# f1c200s_V1_1.net
KiCad netlist of a schematic drawn in EasyEDA Pro
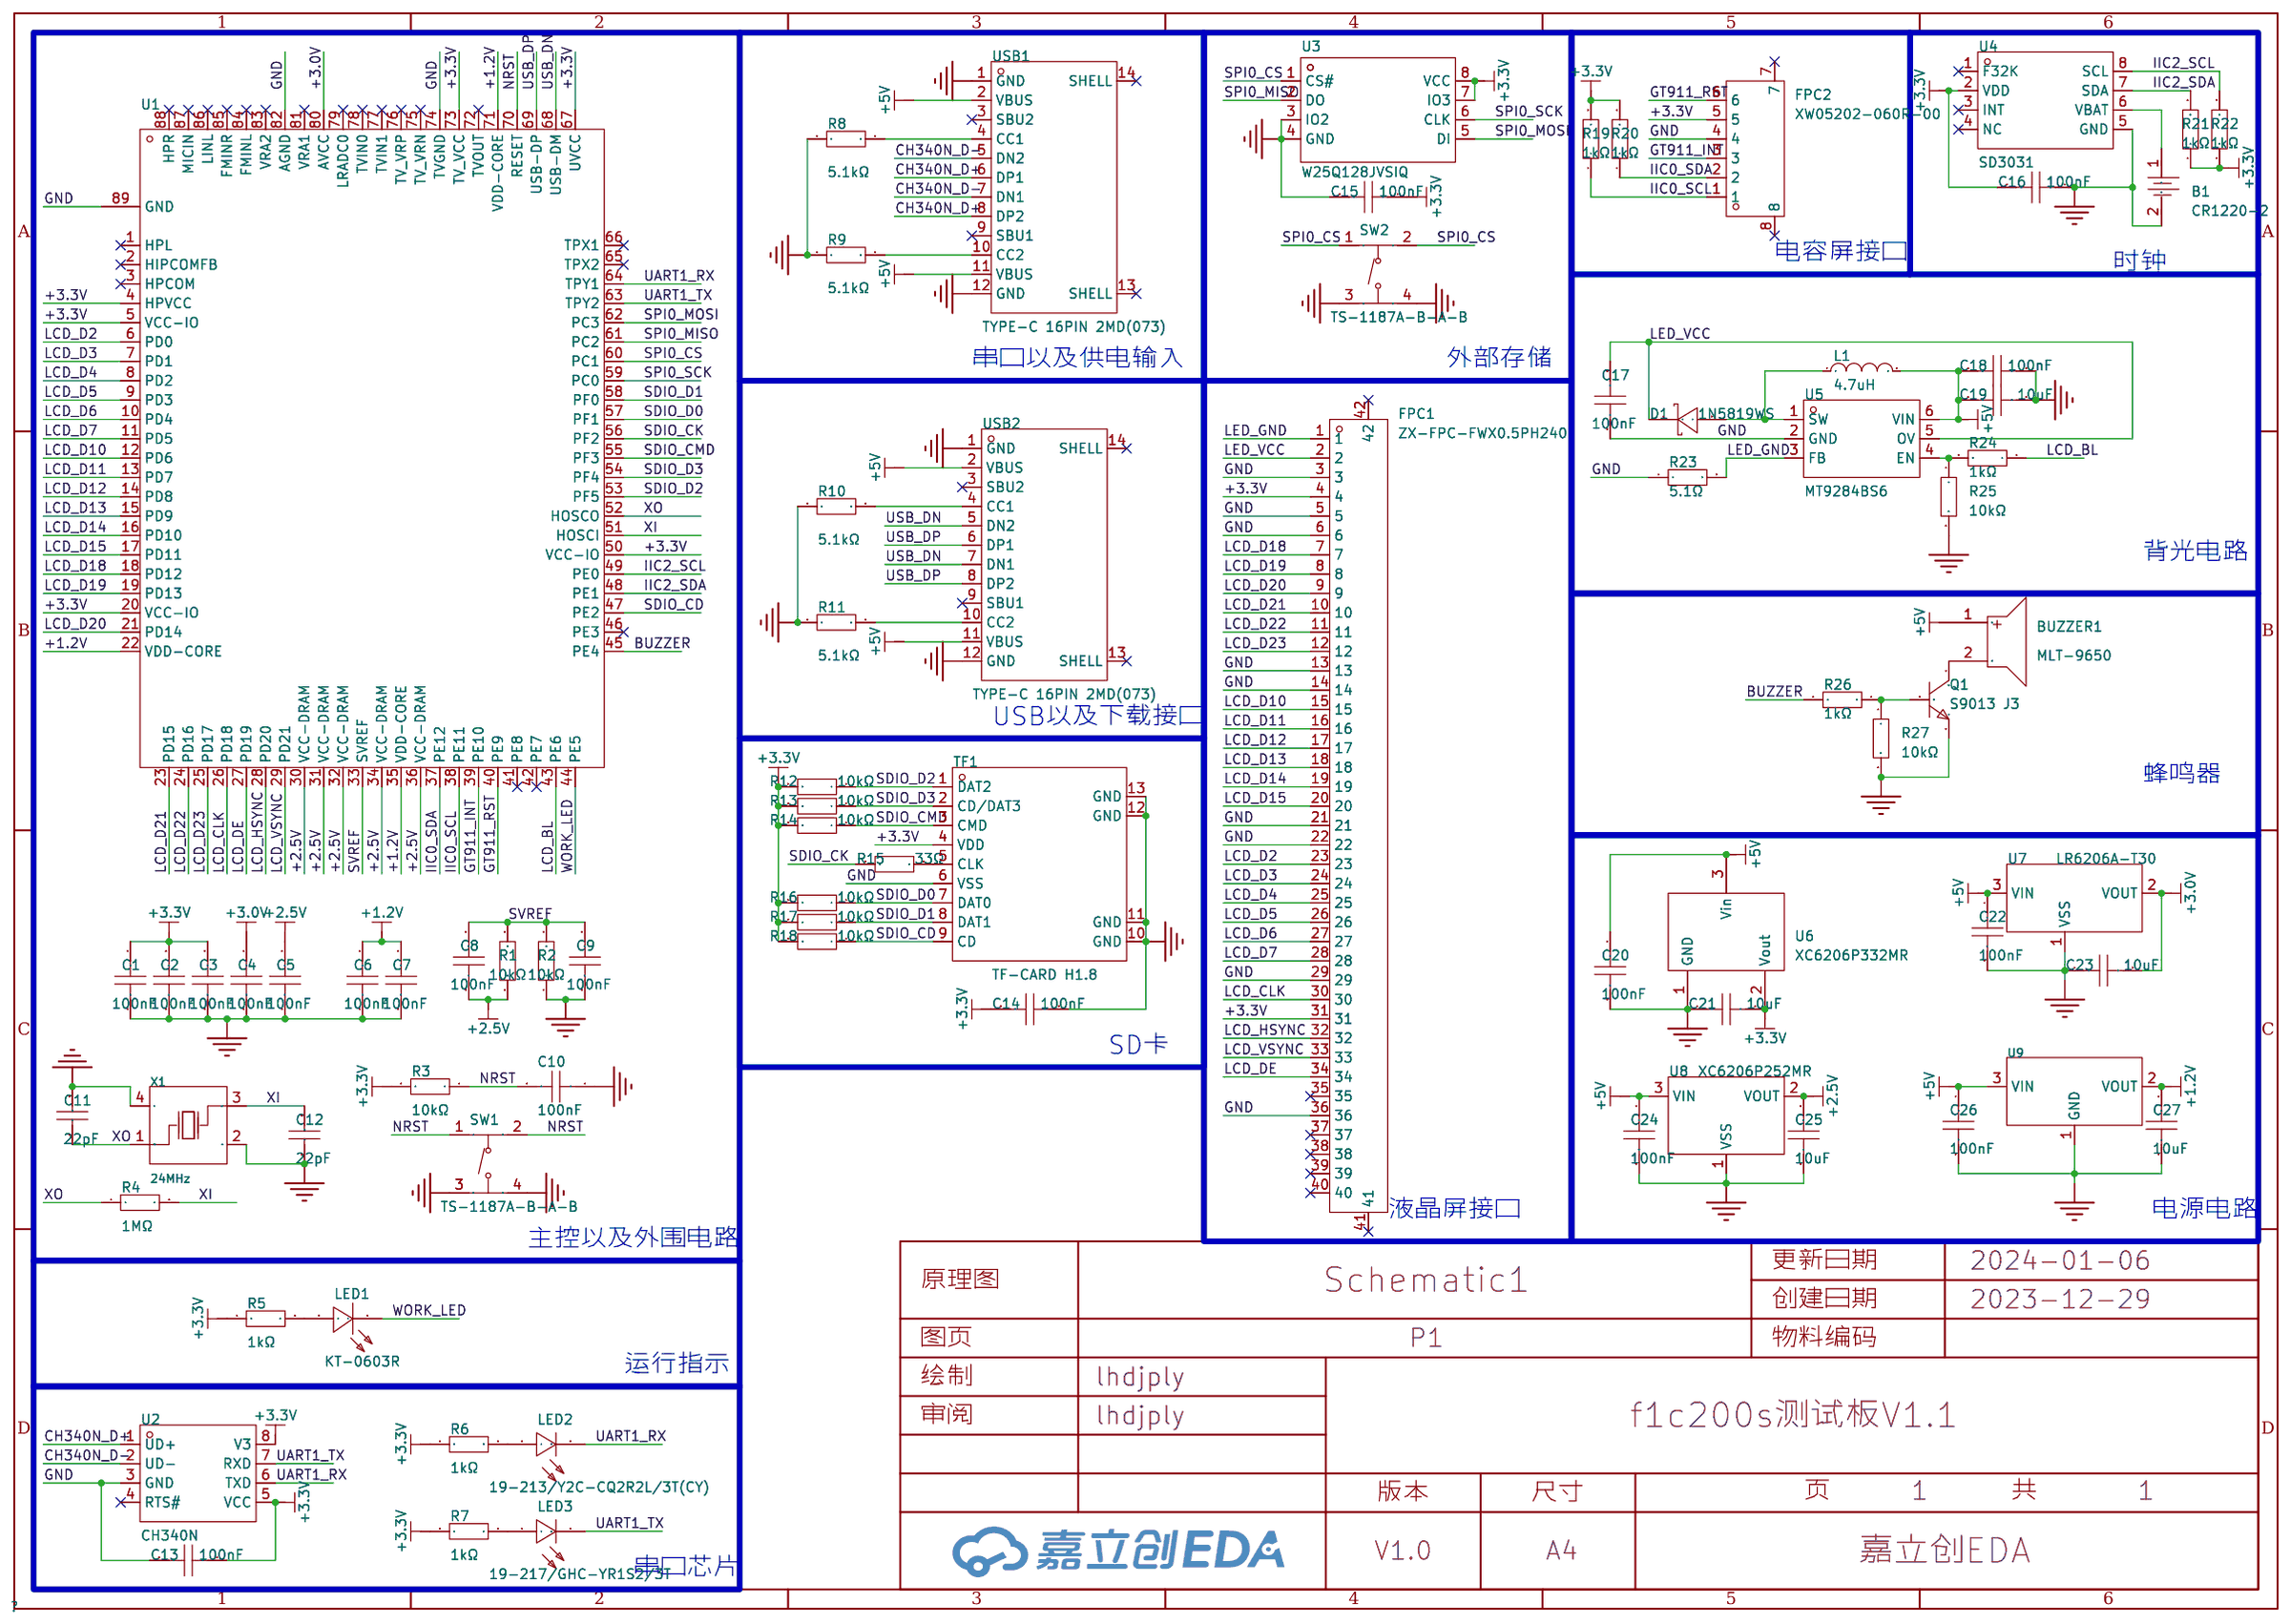
[diagram p0: schematic sheet]

(export (version "E")
  (design (tool "Eeschema 10.0.6"))
  (components
    (comp (ref "B1")
      (value "CR1220-2")
      (footprint "easyedapro:BAT-SMD_CR1220-2")
      (description "连接器类型:电池底座;适用电池规格:CR1220;工作温度范围:-;")
      (fields (field (name "Manufacturer") "Q&amp;J"))
      (libsource (lib "easyedapro") (part "CR1220-2"))
    )
    (comp (ref "BUZZER1")
      (value "2700Hz")
      (footprint "easyedapro:BUZ-SMD_L9.6-W9.6-LS10.0-R")
      (fields (field (name "Manufacturer Part") "MLT-9650") (field (name "Manufacturer") "华能"))
      (libsource (lib "easyedapro") (part "HND-9650B"))
    )
    (comp (ref "C1")
      (value "100nF")
      (footprint "easyedapro:C0603")
      (description "容值:100nF;精度:±10%;额定电压:50V;材质(温度系数):X7R;")
      (fields
        (field (name "Manufacturer Part") "CC0603KRX7R9BB104")
        (field (name "Manufacturer") "YAGEO(国巨)")
      )
      (libsource (lib "easyedapro") (part "CC0603KRX7R9BB104"))
    )
    (comp (ref "C2")
      (value "100nF")
      (footprint "easyedapro:C0603")
      (description "容值:100nF;精度:±10%;额定电压:50V;材质(温度系数):X7R;")
      (fields
        (field (name "Manufacturer Part") "CC0603KRX7R9BB104")
        (field (name "Manufacturer") "YAGEO(国巨)")
      )
      (libsource (lib "easyedapro") (part "CC0603KRX7R9BB104"))
    )
    (comp (ref "C3")
      (value "100nF")
      (footprint "easyedapro:C0603")
      (description "容值:100nF;精度:±10%;额定电压:50V;材质(温度系数):X7R;")
      (fields
        (field (name "Manufacturer Part") "CC0603KRX7R9BB104")
        (field (name "Manufacturer") "YAGEO(国巨)")
      )
      (libsource (lib "easyedapro") (part "CC0603KRX7R9BB104"))
    )
    (comp (ref "C4")
      (value "100nF")
      (footprint "easyedapro:C0603")
      (description "容值:100nF;精度:±10%;额定电压:50V;材质(温度系数):X7R;")
      (fields
        (field (name "Manufacturer Part") "CC0603KRX7R9BB104")
        (field (name "Manufacturer") "YAGEO(国巨)")
      )
      (libsource (lib "easyedapro") (part "CC0603KRX7R9BB104"))
    )
    (comp (ref "C5")
      (value "100nF")
      (footprint "easyedapro:C0603")
      (description "容值:100nF;精度:±10%;额定电压:50V;材质(温度系数):X7R;")
      (fields
        (field (name "Manufacturer Part") "CC0603KRX7R9BB104")
        (field (name "Manufacturer") "YAGEO(国巨)")
      )
      (libsource (lib "easyedapro") (part "CC0603KRX7R9BB104"))
    )
    (comp (ref "C6")
      (value "100nF")
      (footprint "easyedapro:C0603")
      (description "容值:100nF;精度:±10%;额定电压:50V;材质(温度系数):X7R;")
      (fields
        (field (name "Manufacturer Part") "CC0603KRX7R9BB104")
        (field (name "Manufacturer") "YAGEO(国巨)")
      )
      (libsource (lib "easyedapro") (part "CC0603KRX7R9BB104"))
    )
    (comp (ref "C7")
      (value "100nF")
      (footprint "easyedapro:C0603")
      (description "容值:100nF;精度:±10%;额定电压:50V;材质(温度系数):X7R;")
      (fields
        (field (name "Manufacturer Part") "CC0603KRX7R9BB104")
        (field (name "Manufacturer") "YAGEO(国巨)")
      )
      (libsource (lib "easyedapro") (part "CC0603KRX7R9BB104"))
    )
    (comp (ref "C8")
      (value "100nF")
      (footprint "easyedapro:C0603")
      (description "容值:100nF;精度:±10%;额定电压:50V;材质(温度系数):X7R;")
      (fields
        (field (name "Manufacturer Part") "CC0603KRX7R9BB104")
        (field (name "Manufacturer") "YAGEO(国巨)")
      )
      (libsource (lib "easyedapro") (part "CC0603KRX7R9BB104"))
    )
    (comp (ref "C9")
      (value "100nF")
      (footprint "easyedapro:C0603")
      (description "容值:100nF;精度:±10%;额定电压:50V;材质(温度系数):X7R;")
      (fields
        (field (name "Manufacturer Part") "CC0603KRX7R9BB104")
        (field (name "Manufacturer") "YAGEO(国巨)")
      )
      (libsource (lib "easyedapro") (part "CC0603KRX7R9BB104"))
    )
    (comp (ref "C10")
      (value "100nF")
      (footprint "easyedapro:C0603")
      (description "容值:100nF;精度:±10%;额定电压:50V;材质(温度系数):X7R;")
      (fields
        (field (name "Manufacturer Part") "CC0603KRX7R9BB104")
        (field (name "Manufacturer") "YAGEO(国巨)")
      )
      (libsource (lib "easyedapro") (part "CC0603KRX7R9BB104"))
    )
    (comp (ref "C11")
      (value "22pF")
      (footprint "easyedapro:C0603")
      (description "容值:22pF;精度:±5%;额定电压:50V;材质(温度系数):C0G;")
      (fields
        (field (name "Manufacturer Part") "CL10C220JB8NNNC")
        (field (name "Manufacturer") "SAMSUNG(三星)")
      )
      (libsource (lib "easyedapro") (part "CL10C220JB8NNNC"))
    )
    (comp (ref "C12")
      (value "22pF")
      (footprint "easyedapro:C0603")
      (description "容值:22pF;精度:±5%;额定电压:50V;材质(温度系数):C0G;")
      (fields
        (field (name "Manufacturer Part") "CL10C220JB8NNNC")
        (field (name "Manufacturer") "SAMSUNG(三星)")
      )
      (libsource (lib "easyedapro") (part "CL10C220JB8NNNC"))
    )
    (comp (ref "C13")
      (value "100nF")
      (footprint "easyedapro:C0603")
      (description "容值:100nF;精度:±10%;额定电压:50V;材质(温度系数):X7R;")
      (fields
        (field (name "Manufacturer Part") "CC0603KRX7R9BB104")
        (field (name "Manufacturer") "YAGEO(国巨)")
      )
      (libsource (lib "easyedapro") (part "CC0603KRX7R9BB104"))
    )
    (comp (ref "C14")
      (value "100nF")
      (footprint "easyedapro:C0603")
      (description "容值:100nF;精度:±10%;额定电压:50V;材质(温度系数):X7R;")
      (fields
        (field (name "Manufacturer Part") "CC0603KRX7R9BB104")
        (field (name "Manufacturer") "YAGEO(国巨)")
      )
      (libsource (lib "easyedapro") (part "CC0603KRX7R9BB104"))
    )
    (comp (ref "C15")
      (value "100nF")
      (footprint "easyedapro:C0603")
      (description "容值:100nF;精度:±10%;额定电压:50V;材质(温度系数):X7R;")
      (fields
        (field (name "Manufacturer Part") "CC0603KRX7R9BB104")
        (field (name "Manufacturer") "YAGEO(国巨)")
      )
      (libsource (lib "easyedapro") (part "CC0603KRX7R9BB104"))
    )
    (comp (ref "C16")
      (value "100nF")
      (footprint "easyedapro:C0603")
      (description "容值:100nF;精度:±10%;额定电压:50V;材质(温度系数):X7R;")
      (fields
        (field (name "Manufacturer Part") "CC0603KRX7R9BB104")
        (field (name "Manufacturer") "YAGEO(国巨)")
      )
      (libsource (lib "easyedapro") (part "CC0603KRX7R9BB104"))
    )
    (comp (ref "C17")
      (value "100nF")
      (footprint "easyedapro:C0603")
      (description "容值:100nF;精度:±10%;额定电压:50V;材质(温度系数):X7R;")
      (fields
        (field (name "Manufacturer Part") "CC0603KRX7R9BB104")
        (field (name "Manufacturer") "YAGEO(国巨)")
      )
      (libsource (lib "easyedapro") (part "CC0603KRX7R9BB104"))
    )
    (comp (ref "C18")
      (value "100nF")
      (footprint "easyedapro:C0603")
      (description "容值:100nF;精度:±10%;额定电压:50V;材质(温度系数):X7R;")
      (fields
        (field (name "Manufacturer Part") "CC0603KRX7R9BB104")
        (field (name "Manufacturer") "YAGEO(国巨)")
      )
      (libsource (lib "easyedapro") (part "CC0603KRX7R9BB104"))
    )
    (comp (ref "C19")
      (value "10uF")
      (footprint "easyedapro:C0603")
      (description "容值:10uF;精度:±10%;额定电压:10V;材质(温度系数):X5R;")
      (fields
        (field (name "Manufacturer Part") "CL10A106KP8NNNC")
        (field (name "Manufacturer") "SAMSUNG(三星)")
      )
      (libsource (lib "easyedapro") (part "CL10A106KP8NNNC"))
    )
    (comp (ref "C20")
      (value "100nF")
      (footprint "easyedapro:C0603")
      (description "容值:100nF;精度:±10%;额定电压:50V;材质(温度系数):X7R;")
      (fields
        (field (name "Manufacturer Part") "CC0603KRX7R9BB104")
        (field (name "Manufacturer") "YAGEO(国巨)")
      )
      (libsource (lib "easyedapro") (part "CC0603KRX7R9BB104"))
    )
    (comp (ref "C21")
      (value "10uF")
      (footprint "easyedapro:C0603")
      (description "容值:10uF;精度:±10%;额定电压:10V;材质(温度系数):X5R;")
      (fields
        (field (name "Manufacturer Part") "CL10A106KP8NNNC")
        (field (name "Manufacturer") "SAMSUNG(三星)")
      )
      (libsource (lib "easyedapro") (part "CL10A106KP8NNNC"))
    )
    (comp (ref "C22")
      (value "100nF")
      (footprint "easyedapro:C0603")
      (description "容值:100nF;精度:±10%;额定电压:50V;材质(温度系数):X7R;")
      (fields
        (field (name "Manufacturer Part") "CC0603KRX7R9BB104")
        (field (name "Manufacturer") "YAGEO(国巨)")
      )
      (libsource (lib "easyedapro") (part "CC0603KRX7R9BB104"))
    )
    (comp (ref "C23")
      (value "10uF")
      (footprint "easyedapro:C0603")
      (description "容值:10uF;精度:±10%;额定电压:10V;材质(温度系数):X5R;")
      (fields
        (field (name "Manufacturer Part") "CL10A106KP8NNNC")
        (field (name "Manufacturer") "SAMSUNG(三星)")
      )
      (libsource (lib "easyedapro") (part "CL10A106KP8NNNC"))
    )
    (comp (ref "C24")
      (value "100nF")
      (footprint "easyedapro:C0603")
      (description "容值:100nF;精度:±10%;额定电压:50V;材质(温度系数):X7R;")
      (fields
        (field (name "Manufacturer Part") "CC0603KRX7R9BB104")
        (field (name "Manufacturer") "YAGEO(国巨)")
      )
      (libsource (lib "easyedapro") (part "CC0603KRX7R9BB104"))
    )
    (comp (ref "C25")
      (value "10uF")
      (footprint "easyedapro:C0603")
      (description "容值:10uF;精度:±10%;额定电压:10V;材质(温度系数):X5R;")
      (fields
        (field (name "Manufacturer Part") "CL10A106KP8NNNC")
        (field (name "Manufacturer") "SAMSUNG(三星)")
      )
      (libsource (lib "easyedapro") (part "CL10A106KP8NNNC"))
    )
    (comp (ref "C26")
      (value "100nF")
      (footprint "easyedapro:C0603")
      (description "容值:100nF;精度:±10%;额定电压:50V;材质(温度系数):X7R;")
      (fields
        (field (name "Manufacturer Part") "CC0603KRX7R9BB104")
        (field (name "Manufacturer") "YAGEO(国巨)")
      )
      (libsource (lib "easyedapro") (part "CC0603KRX7R9BB104"))
    )
    (comp (ref "C27")
      (value "10uF")
      (footprint "easyedapro:C0603")
      (description "容值:10uF;精度:±10%;额定电压:10V;材质(温度系数):X5R;")
      (fields
        (field (name "Manufacturer Part") "CL10A106KP8NNNC")
        (field (name "Manufacturer") "SAMSUNG(三星)")
      )
      (libsource (lib "easyedapro") (part "CL10A106KP8NNNC"))
    )
    (comp (ref "D1")
      (value "1N5819WS")
      (footprint "easyedapro:SOD-323_L1.8-W1.3-LS2.5-RD")
      (description "正向压降(Vf):600mV@1A;直流反向耐压(Vr):40V;平均整流电流(Io):1A;")
      (fields (field (name "Manufacturer") "Hottech(合科泰)"))
      (libsource (lib "easyedapro") (part "1N5819WS"))
    )
    (comp (ref "FPC1")
      (value "ZX-FPC-FWX0.5PH240")
      (footprint "easyedapro:FPC-SMD_40P-P0.50_MEGASTAR_ZX-FPC-FWX0.5PH240")
      (description "间距:0.5mm;触点数量:40P;锁定特性:翻盖式;触点类型:下接;安装类型:卧贴;工作温度范围:-25°C~+85°C;焊接温度(最大值):260°C;")
      (fields (field (name "Manufacturer") "Megastar(兆星)"))
      (libsource (lib "easyedapro") (part "ZX-FPC-FWX0.5PH240"))
    )
    (comp (ref "FPC2")
      (value "XW05202-060R-00")
      (footprint "easyedapro:FPC-SMD_XW05202-060R-00")
      (description "间距:0.5mm;触点数量:6P;锁定特性:翻盖式;触点类型:下接;安装类型:卧贴;工作温度范围:-25°C~+85°C;")
      (fields (field (name "Manufacturer") "HCTL(华灿天禄)"))
      (libsource (lib "easyedapro") (part "XW05202-060R-00"))
    )
    (comp (ref "L1")
      (value "4.7uH")
      (footprint "easyedapro:IND-SMD_L5.8-W5.2_SLF05XX")
      (description "电感值:4.7uH;精度:±20%;额定电流:3A;饱和电流(Isat):3A;")
      (fields (field (name "Manufacturer Part") "CD54N-4R7M") (field (name "Manufacturer") "MINGSTAR(登壹)"))
      (libsource (lib "easyedapro") (part "CD54N-4R7M"))
    )
    (comp (ref "LED1")
      (value "KT-0603R")
      (footprint "easyedapro:LED0603-RD")
      (description "发光颜色:红灯;二极管配置:-;透镜颜色:-;主波长:-;色温:-;功率:-;发光角度:-;安装方式:-;工作温度:-40°C~+85°C;")
      (fields (field (name "Manufacturer") "KENTO"))
      (libsource (lib "easyedapro") (part "KT-0603R"))
    )
    (comp (ref "LED2")
      (value "19-213/Y2C-CQ2R2L/3T(CY)")
      (footprint "easyedapro:LED0603-RD-YELLOW")
      (description "发光颜色:黄灯;二极管配置:-;主波长:585.5nm~591.5nm;色温:-;功率:60mW;安装方式:-;")
      (fields (field (name "Manufacturer") "EVERLIGHT(亿光)"))
      (libsource (lib "easyedapro") (part "19-213/Y2C-CQ2R2L/3T(CY)"))
    )
    (comp (ref "LED3")
      (value "19-217/GHC-YR1S2/3T")
      (footprint "easyedapro:LED0603-RD")
      (fields (field (name "Manufacturer") "EVERLIGHT(亿光)"))
      (libsource (lib "easyedapro") (part "19-217/GHC-YR1S2/3T"))
    )
    (comp (ref "Q1")
      (value "S9013 J3")
      (footprint "easyedapro:SOT-23-3_L2.9-W1.3-P1.90-LS2.4-BR")
      (description "晶体管类型:NPN;集电极电流(Ic):500mA;集射极击穿电压(Vceo):25V;功率(Pd):300mW;直流电流增益(hFE@Ic,Vce):200@50mA,1V;")
      (fields (field (name "Manufacturer") "CJ(江苏长电/长晶)"))
      (libsource (lib "easyedapro") (part "S9013 J3"))
    )
    (comp (ref "R1")
      (value "10kΩ")
      (footprint "easyedapro:R0603")
      (description "阻值:10kΩ;精度:±1%;功率:100mW;温度系数:±100ppm/°C;电阻类型:厚膜电阻;")
      (fields
        (field (name "Manufacturer Part") "0603WAF1002T5E")
        (field (name "Manufacturer") "UNI-ROYAL(厚声)")
      )
      (libsource (lib "easyedapro") (part "0603WAF1002T5E"))
    )
    (comp (ref "R2")
      (value "10kΩ")
      (footprint "easyedapro:R0603")
      (description "阻值:10kΩ;精度:±1%;功率:100mW;温度系数:±100ppm/°C;电阻类型:厚膜电阻;")
      (fields
        (field (name "Manufacturer Part") "0603WAF1002T5E")
        (field (name "Manufacturer") "UNI-ROYAL(厚声)")
      )
      (libsource (lib "easyedapro") (part "0603WAF1002T5E"))
    )
    (comp (ref "R3")
      (value "10kΩ")
      (footprint "easyedapro:R0603")
      (description "阻值:10kΩ;精度:±1%;功率:100mW;温度系数:±100ppm/°C;电阻类型:厚膜电阻;")
      (fields
        (field (name "Manufacturer Part") "0603WAF1002T5E")
        (field (name "Manufacturer") "UNI-ROYAL(厚声)")
      )
      (libsource (lib "easyedapro") (part "0603WAF1002T5E"))
    )
    (comp (ref "R4")
      (value "1MΩ")
      (footprint "easyedapro:R0603")
      (description "阻值:1MΩ;精度:±1%;功率:100mW;温度系数:±100ppm/°C;电阻类型:厚膜电阻;")
      (fields
        (field (name "Manufacturer Part") "0603WAF1004T5E")
        (field (name "Manufacturer") "UNI-ROYAL(厚声)")
      )
      (libsource (lib "easyedapro") (part "0603WAF1004T5E"))
    )
    (comp (ref "R5")
      (value "1kΩ")
      (footprint "easyedapro:R0603")
      (description "阻值:1kΩ;精度:±1%;功率:100mW;温度系数:±100ppm/°C;电阻类型:厚膜电阻;")
      (fields
        (field (name "Manufacturer Part") "0603WAF1001T5E")
        (field (name "Manufacturer") "UNI-ROYAL(厚声)")
      )
      (libsource (lib "easyedapro") (part "0603WAF1001T5E"))
    )
    (comp (ref "R6")
      (value "1kΩ")
      (footprint "easyedapro:R0603")
      (description "阻值:1kΩ;精度:±1%;功率:100mW;温度系数:±100ppm/°C;电阻类型:厚膜电阻;")
      (fields
        (field (name "Manufacturer Part") "0603WAF1001T5E")
        (field (name "Manufacturer") "UNI-ROYAL(厚声)")
      )
      (libsource (lib "easyedapro") (part "0603WAF1001T5E"))
    )
    (comp (ref "R7")
      (value "1kΩ")
      (footprint "easyedapro:R0603")
      (description "阻值:1kΩ;精度:±1%;功率:100mW;温度系数:±100ppm/°C;电阻类型:厚膜电阻;")
      (fields
        (field (name "Manufacturer Part") "0603WAF1001T5E")
        (field (name "Manufacturer") "UNI-ROYAL(厚声)")
      )
      (libsource (lib "easyedapro") (part "0603WAF1001T5E"))
    )
    (comp (ref "R8")
      (value "5.1kΩ")
      (footprint "easyedapro:R0603")
      (description "阻值:5.1kΩ;精度:±1%;功率:100mW;温度系数:±100ppm/°C;电阻类型:厚膜电阻;")
      (fields
        (field (name "Manufacturer Part") "0603WAF5101T5E")
        (field (name "Manufacturer") "UNI-ROYAL(厚声)")
      )
      (libsource (lib "easyedapro") (part "0603WAF5101T5E"))
    )
    (comp (ref "R9")
      (value "5.1kΩ")
      (footprint "easyedapro:R0603")
      (description "阻值:5.1kΩ;精度:±1%;功率:100mW;温度系数:±100ppm/°C;电阻类型:厚膜电阻;")
      (fields
        (field (name "Manufacturer Part") "0603WAF5101T5E")
        (field (name "Manufacturer") "UNI-ROYAL(厚声)")
      )
      (libsource (lib "easyedapro") (part "0603WAF5101T5E"))
    )
    (comp (ref "R10")
      (value "5.1kΩ")
      (footprint "easyedapro:R0603")
      (description "阻值:5.1kΩ;精度:±1%;功率:100mW;温度系数:±100ppm/°C;电阻类型:厚膜电阻;")
      (fields
        (field (name "Manufacturer Part") "0603WAF5101T5E")
        (field (name "Manufacturer") "UNI-ROYAL(厚声)")
      )
      (libsource (lib "easyedapro") (part "0603WAF5101T5E"))
    )
    (comp (ref "R11")
      (value "5.1kΩ")
      (footprint "easyedapro:R0603")
      (description "阻值:5.1kΩ;精度:±1%;功率:100mW;温度系数:±100ppm/°C;电阻类型:厚膜电阻;")
      (fields
        (field (name "Manufacturer Part") "0603WAF5101T5E")
        (field (name "Manufacturer") "UNI-ROYAL(厚声)")
      )
      (libsource (lib "easyedapro") (part "0603WAF5101T5E"))
    )
    (comp (ref "R12")
      (value "10kΩ")
      (footprint "easyedapro:R0603")
      (description "阻值:10kΩ;精度:±1%;功率:100mW;温度系数:±100ppm/°C;电阻类型:厚膜电阻;")
      (fields
        (field (name "Manufacturer Part") "0603WAF1002T5E")
        (field (name "Manufacturer") "UNI-ROYAL(厚声)")
      )
      (libsource (lib "easyedapro") (part "0603WAF1002T5E"))
    )
    (comp (ref "R13")
      (value "10kΩ")
      (footprint "easyedapro:R0603")
      (description "阻值:10kΩ;精度:±1%;功率:100mW;温度系数:±100ppm/°C;电阻类型:厚膜电阻;")
      (fields
        (field (name "Manufacturer Part") "0603WAF1002T5E")
        (field (name "Manufacturer") "UNI-ROYAL(厚声)")
      )
      (libsource (lib "easyedapro") (part "0603WAF1002T5E"))
    )
    (comp (ref "R14")
      (value "10kΩ")
      (footprint "easyedapro:R0603")
      (description "阻值:10kΩ;精度:±1%;功率:100mW;温度系数:±100ppm/°C;电阻类型:厚膜电阻;")
      (fields
        (field (name "Manufacturer Part") "0603WAF1002T5E")
        (field (name "Manufacturer") "UNI-ROYAL(厚声)")
      )
      (libsource (lib "easyedapro") (part "0603WAF1002T5E"))
    )
    (comp (ref "R15")
      (value "33Ω")
      (footprint "easyedapro:R0603")
      (description "阻值:33Ω;精度:±1%;功率:100mW;温度系数:±100ppm/°C;电阻类型:厚膜电阻;")
      (fields
        (field (name "Manufacturer Part") "0603WAF330JT5E")
        (field (name "Manufacturer") "UNI-ROYAL(厚声)")
      )
      (libsource (lib "easyedapro") (part "0603WAF330JT5E"))
    )
    (comp (ref "R16")
      (value "10kΩ")
      (footprint "easyedapro:R0603")
      (description "阻值:10kΩ;精度:±1%;功率:100mW;温度系数:±100ppm/°C;电阻类型:厚膜电阻;")
      (fields
        (field (name "Manufacturer Part") "0603WAF1002T5E")
        (field (name "Manufacturer") "UNI-ROYAL(厚声)")
      )
      (libsource (lib "easyedapro") (part "0603WAF1002T5E"))
    )
    (comp (ref "R17")
      (value "10kΩ")
      (footprint "easyedapro:R0603")
      (description "阻值:10kΩ;精度:±1%;功率:100mW;温度系数:±100ppm/°C;电阻类型:厚膜电阻;")
      (fields
        (field (name "Manufacturer Part") "0603WAF1002T5E")
        (field (name "Manufacturer") "UNI-ROYAL(厚声)")
      )
      (libsource (lib "easyedapro") (part "0603WAF1002T5E"))
    )
    (comp (ref "R18")
      (value "10kΩ")
      (footprint "easyedapro:R0603")
      (description "阻值:10kΩ;精度:±1%;功率:100mW;温度系数:±100ppm/°C;电阻类型:厚膜电阻;")
      (fields
        (field (name "Manufacturer Part") "0603WAF1002T5E")
        (field (name "Manufacturer") "UNI-ROYAL(厚声)")
      )
      (libsource (lib "easyedapro") (part "0603WAF1002T5E"))
    )
    (comp (ref "R19")
      (value "1kΩ")
      (footprint "easyedapro:R0603")
      (description "阻值:1kΩ;精度:±1%;功率:100mW;温度系数:±100ppm/°C;电阻类型:厚膜电阻;")
      (fields
        (field (name "Manufacturer Part") "0603WAF1001T5E")
        (field (name "Manufacturer") "UNI-ROYAL(厚声)")
      )
      (libsource (lib "easyedapro") (part "0603WAF1001T5E"))
    )
    (comp (ref "R20")
      (value "1kΩ")
      (footprint "easyedapro:R0603")
      (description "阻值:1kΩ;精度:±1%;功率:100mW;温度系数:±100ppm/°C;电阻类型:厚膜电阻;")
      (fields
        (field (name "Manufacturer Part") "0603WAF1001T5E")
        (field (name "Manufacturer") "UNI-ROYAL(厚声)")
      )
      (libsource (lib "easyedapro") (part "0603WAF1001T5E"))
    )
    (comp (ref "R21")
      (value "1kΩ")
      (footprint "easyedapro:R0603")
      (description "阻值:1kΩ;精度:±1%;功率:100mW;温度系数:±100ppm/°C;电阻类型:厚膜电阻;")
      (fields
        (field (name "Manufacturer Part") "0603WAF1001T5E")
        (field (name "Manufacturer") "UNI-ROYAL(厚声)")
      )
      (libsource (lib "easyedapro") (part "0603WAF1001T5E"))
    )
    (comp (ref "R22")
      (value "1kΩ")
      (footprint "easyedapro:R0603")
      (description "阻值:1kΩ;精度:±1%;功率:100mW;温度系数:±100ppm/°C;电阻类型:厚膜电阻;")
      (fields
        (field (name "Manufacturer Part") "0603WAF1001T5E")
        (field (name "Manufacturer") "UNI-ROYAL(厚声)")
      )
      (libsource (lib "easyedapro") (part "0603WAF1001T5E"))
    )
    (comp (ref "R23")
      (value "5.1Ω")
      (footprint "easyedapro:R0603")
      (description "阻值:5.1Ω;精度:±1%;功率:100mW;温度系数:±200ppm/°C;电阻类型:厚膜电阻;")
      (fields
        (field (name "Manufacturer Part") "0603WAF510KT5E")
        (field (name "Manufacturer") "UNI-ROYAL(厚声)")
      )
      (libsource (lib "easyedapro") (part "0603WAF510KT5E"))
    )
    (comp (ref "R24")
      (value "1kΩ")
      (footprint "easyedapro:R0603")
      (description "阻值:1kΩ;精度:±1%;功率:100mW;温度系数:±100ppm/°C;电阻类型:厚膜电阻;")
      (fields
        (field (name "Manufacturer Part") "0603WAF1001T5E")
        (field (name "Manufacturer") "UNI-ROYAL(厚声)")
      )
      (libsource (lib "easyedapro") (part "0603WAF1001T5E"))
    )
    (comp (ref "R25")
      (value "10kΩ")
      (footprint "easyedapro:R0603")
      (description "阻值:10kΩ;精度:±1%;功率:100mW;温度系数:±100ppm/°C;电阻类型:厚膜电阻;")
      (fields
        (field (name "Manufacturer Part") "0603WAF1002T5E")
        (field (name "Manufacturer") "UNI-ROYAL(厚声)")
      )
      (libsource (lib "easyedapro") (part "0603WAF1002T5E"))
    )
    (comp (ref "R26")
      (value "1kΩ")
      (footprint "easyedapro:R0603")
      (description "阻值:1kΩ;精度:±1%;功率:100mW;温度系数:±100ppm/°C;电阻类型:厚膜电阻;")
      (fields
        (field (name "Manufacturer Part") "0603WAF1001T5E")
        (field (name "Manufacturer") "UNI-ROYAL(厚声)")
      )
      (libsource (lib "easyedapro") (part "0603WAF1001T5E"))
    )
    (comp (ref "R27")
      (value "10kΩ")
      (footprint "easyedapro:R0603")
      (description "阻值:10kΩ;精度:±1%;功率:100mW;温度系数:±100ppm/°C;电阻类型:厚膜电阻;")
      (fields
        (field (name "Manufacturer Part") "0603WAF1002T5E")
        (field (name "Manufacturer") "UNI-ROYAL(厚声)")
      )
      (libsource (lib "easyedapro") (part "0603WAF1002T5E"))
    )
    (comp (ref "SW1")
      (value "TS-1187A-B-A-B")
      (footprint "easyedapro:SW-SMD_4P-L5.1-W5.1-P3.70-LS6.5-TL-2")
      (description "触点电流:50mA;额定电压(DC):12V;绝缘电阻:-;电路结构:单刀单掷;安装方式:立贴;带灯:无;作用力:160gf;机械寿命:10万次;带支架:否;")
      (fields (field (name "Manufacturer") "XKB Connectivity(中国星坤)"))
      (libsource (lib "easyedapro") (part "TS-1187A-B-A-B"))
    )
    (comp (ref "SW2")
      (value "TS-1187A-B-A-B")
      (footprint "easyedapro:SW-SMD_4P-L5.1-W5.1-P3.70-LS6.5-TL-2")
      (description "触点电流:50mA;额定电压(DC):12V;绝缘电阻:-;电路结构:单刀单掷;安装方式:立贴;带灯:无;作用力:160gf;机械寿命:10万次;带支架:否;")
      (fields (field (name "Manufacturer") "XKB Connectivity(中国星坤)"))
      (libsource (lib "easyedapro") (part "TS-1187A-B-A-B"))
    )
    (comp (ref "TF1")
      (value "TF-CARD H1.8")
      (footprint "easyedapro:TF-SMD_TF-CARD-H1.8")
      (description "卡连接方式:自弹式;卡类型:MicroSD卡(TF卡);连接器类型:卡座;本体最大高度:1.8mm;触头材质:铜合金;触头镀层:金;工作温度范围:-40°C~+70°C;")
      (fields (field (name "Manufacturer") "SHOU HAN(首韩)"))
      (libsource (lib "easyedapro") (part "TF-CARD H1.8"))
    )
    (comp (ref "U1")
      (value "F1C200S")
      (footprint "easyedapro:QFN-88_L10.0-W10.0-P0.40-BL-EP6.75")
      (description "CPU内核:-;GPIO端口数量:-;工作电压范围:-;CPU最大主频:-;程序存储器类型:-;")
      (fields (field (name "Manufacturer") "Allwinner(全志)"))
      (libsource (lib "easyedapro") (part "F1C200S"))
    )
    (comp (ref "U2")
      (value "CH340N")
      (footprint "easyedapro:SOP-8_L4.9-W3.9-P1.27-LS6.0-BL")
      (fields (field (name "Manufacturer") "WCH(南京沁恒)"))
      (libsource (lib "easyedapro") (part "CH340N_C2977777"))
    )
    (comp (ref "U3")
      (value "W25Q128JVSIQ")
      (footprint "easyedapro:SOIC-8_L5.3-W5.3-P1.27-LS8.0-BL")
      (description "接口类型:-;存储容量:128Mbit;时钟频率(fc):-;")
      (fields (field (name "Manufacturer") "WINBOND(华邦)"))
      (libsource (lib "easyedapro") (part "W25Q128JVSIQTR"))
    )
    (comp (ref "U4")
      (value "SD3031")
      (footprint "easyedapro:SOP-8_L5.3-W5.3-P1.27-LS8.0-BL")
      (fields (field (name "Manufacturer") "WAVE(兴威帆电子)"))
      (libsource (lib "easyedapro") (part "SD3031"))
    )
    (comp (ref "U5")
      (value "MT9284BS6")
      (footprint "easyedapro:SOT-23-6_L2.9-W1.6-P0.95-LS2.8-BR")
      (fields (field (name "Manufacturer") "西安航天民芯"))
      (libsource (lib "easyedapro") (part "MT9284BS6"))
    )
    (comp (ref "U6")
      (value "XC6206P332MR")
      (footprint "easyedapro:SOT-23-3_L2.9-W1.6-P1.90-LS2.8-BR")
      (description "输出类型:固定;输出极性:正;最大输入电压:6V;输出电压:3.3V;输出电流:200mA;电源纹波抑制比(PSRR):-;")
      (fields (field (name "Manufacturer") "TOREX(特瑞仕)"))
      (libsource (lib "easyedapro") (part "XC6206P332MR"))
    )
    (comp (ref "U7")
      (value "LR6206A-T30")
      (footprint "easyedapro:SOT-23-3_L2.9-W1.3-P1.90-LS2.4-BR")
      (description "输出类型:固定;最大输入电压:6.5V;输出电压:3V;输出电流:300mA;电源纹波抑制比(PSRR):55dB@(1kHz);输出极性:正;")
      (fields (field (name "Manufacturer") "LR(朗瑞)"))
      (libsource (lib "easyedapro") (part "LR6206A-T30"))
    )
    (comp (ref "U8")
      (value "XC6206P252MR")
      (footprint "easyedapro:SOT-23-3_L2.9-W1.3-P1.90-LS2.4-BR")
      (description "输出类型:固定;最大输入电压:8V;输出电压:2.5V;输出电流:300mA;输出极性:正;")
      (fields (field (name "Manufacturer") "HXY MOSFET(华轩阳电子)"))
      (libsource (lib "easyedapro") (part "XC6206P252MR_C5148689"))
    )
    (comp (ref "U9")
      (value "LR8103A-T12")
      (footprint "easyedapro:SOT-23-3_L2.9-W1.6-P1.90-LS2.8-BR")
      (description "输出类型:-;最大输入电压:-;输出电压:1.2V;输出电流:300mA;电源纹波抑制比(PSRR):-;输出极性:-;")
      (fields (field (name "Manufacturer") "LR(朗瑞)"))
      (libsource (lib "easyedapro") (part "LR8103A-T12"))
    )
    (comp (ref "USB1")
      (value "TYPE-C 16PIN 2MD(073)")
      (footprint "easyedapro:USB-C-SMD_TYPE-C-6PIN-2MD-073")
      (description "连接器类型:Type-C;标准:-;公母:母;端口数量:1;触点数量:16P;安装方式:卧贴;额定电流 - 电源:5A;工作温度范围:-25°C~+85°C;")
      (fields (field (name "Manufacturer") "SHOU HAN(首韩)"))
      (libsource (lib "easyedapro") (part "TYPE-C 16PIN 2MD(073)"))
    )
    (comp (ref "USB2")
      (value "TYPE-C 16PIN 2MD(073)")
      (footprint "easyedapro:USB-C-SMD_TYPE-C-6PIN-2MD-073")
      (description "连接器类型:Type-C;标准:-;公母:母;端口数量:1;触点数量:16P;安装方式:卧贴;额定电流 - 电源:5A;工作温度范围:-25°C~+85°C;")
      (fields (field (name "Manufacturer") "SHOU HAN(首韩)"))
      (libsource (lib "easyedapro") (part "TYPE-C 16PIN 2MD(073)"))
    )
    (comp (ref "X1")
      (value "24MHz")
      (footprint "easyedapro:CRYSTAL-SMD_4P-L3.2-W2.5-BL-2")
      (description "频率:24MHz;频率公差:±10ppm;负载电容:20pF;")
      (fields (field (name "Manufacturer Part") "K3A240002010") (field (name "Manufacturer") "KYX(凯越翔电子)"))
      (libsource (lib "easyedapro") (part "K3A240002010"))
    )
  )
  (nets
    (net (code "1") (name "+1.2V") (class "Default")
      (node (ref "C27") (pin "2") (pinfunction "2_2") (pintype "unspecified"))
      (node (ref "C6") (pin "2") (pinfunction "2_2") (pintype "unspecified"))
      (node (ref "C7") (pin "2") (pinfunction "2_2") (pintype "unspecified"))
      (node (ref "U1") (pin "22") (pinfunction "VDD-CORE_22") (pintype "unspecified"))
      (node (ref "U1") (pin "35") (pinfunction "VDD-CORE_35") (pintype "unspecified"))
      (node (ref "U1") (pin "71") (pinfunction "VDD-CORE_71") (pintype "unspecified"))
      (node (ref "U9") (pin "2") (pinfunction "VOUT_2") (pintype "input"))
    )
    (net (code "2") (name "+2.5V") (class "Default")
      (node (ref "C25") (pin "2") (pinfunction "2_2") (pintype "unspecified"))
      (node (ref "C5") (pin "2") (pinfunction "2_2") (pintype "unspecified"))
      (node (ref "C8") (pin "1") (pinfunction "1_1") (pintype "unspecified"))
      (node (ref "R1") (pin "1") (pinfunction "1_1") (pintype "input"))
      (node (ref "U1") (pin "30") (pinfunction "VCC-DRAM_30") (pintype "unspecified"))
      (node (ref "U1") (pin "31") (pinfunction "VCC-DRAM_31") (pintype "unspecified"))
      (node (ref "U1") (pin "32") (pinfunction "VCC-DRAM_32") (pintype "unspecified"))
      (node (ref "U1") (pin "34") (pinfunction "VCC-DRAM_34") (pintype "unspecified"))
      (node (ref "U1") (pin "36") (pinfunction "VCC-DRAM_36") (pintype "unspecified"))
      (node (ref "U8") (pin "2") (pinfunction "VOUT_2") (pintype "unspecified"))
    )
    (net (code "3") (name "+3.0V") (class "Default")
      (node (ref "C23") (pin "2") (pinfunction "2_2") (pintype "unspecified"))
      (node (ref "C4") (pin "2") (pinfunction "2_2") (pintype "unspecified"))
      (node (ref "U1") (pin "80") (pinfunction "AVCC_80") (pintype "unspecified"))
      (node (ref "U7") (pin "2") (pinfunction "VOUT_2") (pintype "unspecified"))
    )
    (net (code "4") (name "+3.3V") (class "Default")
      (node (ref "C1") (pin "2") (pinfunction "2_2") (pintype "unspecified"))
      (node (ref "C13") (pin "1") (pinfunction "1_1") (pintype "unspecified"))
      (node (ref "C14") (pin "2") (pinfunction "2_2") (pintype "unspecified"))
      (node (ref "C15") (pin "1") (pinfunction "1_1") (pintype "unspecified"))
      (node (ref "C16") (pin "2") (pinfunction "2_2") (pintype "unspecified"))
      (node (ref "C2") (pin "2") (pinfunction "2_2") (pintype "unspecified"))
      (node (ref "C21") (pin "2") (pinfunction "2_2") (pintype "unspecified"))
      (node (ref "C3") (pin "2") (pinfunction "2_2") (pintype "unspecified"))
      (node (ref "FPC1") (pin "31") (pinfunction "31_31") (pintype "unspecified"))
      (node (ref "FPC1") (pin "4") (pinfunction "4_4") (pintype "unspecified"))
      (node (ref "FPC2") (pin "5") (pinfunction "5_5") (pintype "unspecified"))
      (node (ref "R12") (pin "2") (pinfunction "2_2") (pintype "input"))
      (node (ref "R13") (pin "2") (pinfunction "2_2") (pintype "input"))
      (node (ref "R14") (pin "2") (pinfunction "2_2") (pintype "input"))
      (node (ref "R16") (pin "2") (pinfunction "2_2") (pintype "input"))
      (node (ref "R17") (pin "2") (pinfunction "2_2") (pintype "input"))
      (node (ref "R18") (pin "2") (pinfunction "2_2") (pintype "input"))
      (node (ref "R19") (pin "2") (pinfunction "2_2") (pintype "input"))
      (node (ref "R20") (pin "2") (pinfunction "2_2") (pintype "input"))
      (node (ref "R21") (pin "1") (pinfunction "1_1") (pintype "input"))
      (node (ref "R22") (pin "1") (pinfunction "1_1") (pintype "input"))
      (node (ref "R3") (pin "2") (pinfunction "2_2") (pintype "input"))
      (node (ref "R5") (pin "1") (pinfunction "1_1") (pintype "input"))
      (node (ref "R6") (pin "1") (pinfunction "1_1") (pintype "input"))
      (node (ref "R7") (pin "1") (pinfunction "1_1") (pintype "input"))
      (node (ref "TF1") (pin "4") (pinfunction "VDD_4") (pintype "unspecified"))
      (node (ref "U1") (pin "20") (pinfunction "VCC-IO_20") (pintype "unspecified"))
      (node (ref "U1") (pin "4") (pinfunction "HPVCC_4") (pintype "unspecified"))
      (node (ref "U1") (pin "5") (pinfunction "VCC-IO_5") (pintype "unspecified"))
      (node (ref "U1") (pin "50") (pinfunction "VCC-IO_50") (pintype "unspecified"))
      (node (ref "U1") (pin "67") (pinfunction "UVCC_67") (pintype "unspecified"))
      (node (ref "U1") (pin "73") (pinfunction "TV_VCC_73") (pintype "unspecified"))
      (node (ref "U2") (pin "5") (pinfunction "VCC_5") (pintype "unspecified"))
      (node (ref "U2") (pin "8") (pinfunction "V3_8") (pintype "unspecified"))
      (node (ref "U3") (pin "7") (pinfunction "IO3_7") (pintype "unspecified"))
      (node (ref "U3") (pin "8") (pinfunction "VCC_8") (pintype "unspecified"))
      (node (ref "U4") (pin "2") (pinfunction "VDD_2") (pintype "unspecified"))
      (node (ref "U6") (pin "2") (pinfunction "Vout_2") (pintype "unspecified"))
    )
    (net (code "5") (name "+5V") (class "Default")
      (node (ref "BUZZER1") (pin "1") (pinfunction "1_1") (pintype "unspecified"))
      (node (ref "C18") (pin "2") (pinfunction "2_2") (pintype "unspecified"))
      (node (ref "C19") (pin "1") (pinfunction "1_1") (pintype "unspecified"))
      (node (ref "C20") (pin "1") (pinfunction "1_1") (pintype "unspecified"))
      (node (ref "C22") (pin "1") (pinfunction "1_1") (pintype "unspecified"))
      (node (ref "C24") (pin "1") (pinfunction "1_1") (pintype "unspecified"))
      (node (ref "C26") (pin "1") (pinfunction "1_1") (pintype "unspecified"))
      (node (ref "L1") (pin "2") (pinfunction "2_2") (pintype "input"))
      (node (ref "U5") (pin "6") (pinfunction "VIN_6") (pintype "input"))
      (node (ref "U6") (pin "3") (pinfunction "Vin_3") (pintype "unspecified"))
      (node (ref "U7") (pin "3") (pinfunction "VIN_3") (pintype "unspecified"))
      (node (ref "U8") (pin "3") (pinfunction "VIN_3") (pintype "unspecified"))
      (node (ref "U9") (pin "3") (pinfunction "VIN_3") (pintype "input"))
      (node (ref "USB1") (pin "11") (pinfunction "VBUS_11") (pintype "unspecified"))
      (node (ref "USB1") (pin "2") (pinfunction "VBUS_2") (pintype "unspecified"))
      (node (ref "USB2") (pin "11") (pinfunction "VBUS_11") (pintype "unspecified"))
      (node (ref "USB2") (pin "2") (pinfunction "VBUS_2") (pintype "unspecified"))
    )
    (net (code "6") (name "/BUZZER") (class "Default")
      (node (ref "R26") (pin "2") (pinfunction "2_2") (pintype "input"))
      (node (ref "U1") (pin "45") (pinfunction "PE4_45") (pintype "unspecified"))
    )
    (net (code "7") (name "/CH340N_D+") (class "Default")
      (node (ref "U2") (pin "1") (pinfunction "UD+_1") (pintype "unspecified"))
      (node (ref "USB1") (pin "6") (pinfunction "DP1_6") (pintype "unspecified"))
      (node (ref "USB1") (pin "8") (pinfunction "DP2_8") (pintype "unspecified"))
    )
    (net (code "8") (name "/CH340N_D-") (class "Default")
      (node (ref "U2") (pin "2") (pinfunction "UD-_2") (pintype "unspecified"))
      (node (ref "USB1") (pin "5") (pinfunction "DN2_5") (pintype "unspecified"))
      (node (ref "USB1") (pin "7") (pinfunction "DN1_7") (pintype "unspecified"))
    )
    (net (code "9") (name "/GT911_INT") (class "Default")
      (node (ref "FPC2") (pin "3") (pinfunction "3_3") (pintype "unspecified"))
      (node (ref "U1") (pin "39") (pinfunction "PE10_39") (pintype "unspecified"))
    )
    (net (code "10") (name "/GT911_RST") (class "Default")
      (node (ref "FPC2") (pin "6") (pinfunction "6_6") (pintype "unspecified"))
      (node (ref "U1") (pin "40") (pinfunction "PE9_40") (pintype "unspecified"))
    )
    (net (code "11") (name "/IIC0_SCL") (class "Default")
      (node (ref "FPC2") (pin "1") (pinfunction "1_1") (pintype "unspecified"))
      (node (ref "R19") (pin "1") (pinfunction "1_1") (pintype "input"))
      (node (ref "U1") (pin "38") (pinfunction "PE11_38") (pintype "unspecified"))
    )
    (net (code "12") (name "/IIC0_SDA") (class "Default")
      (node (ref "FPC2") (pin "2") (pinfunction "2_2") (pintype "unspecified"))
      (node (ref "R20") (pin "1") (pinfunction "1_1") (pintype "input"))
      (node (ref "U1") (pin "37") (pinfunction "PE12_37") (pintype "unspecified"))
    )
    (net (code "13") (name "/IIC2_SCL") (class "Default")
      (node (ref "R22") (pin "2") (pinfunction "2_2") (pintype "input"))
      (node (ref "U1") (pin "49") (pinfunction "PE0_49") (pintype "unspecified"))
      (node (ref "U4") (pin "8") (pinfunction "SCL_8") (pintype "unspecified"))
    )
    (net (code "14") (name "/IIC2_SDA") (class "Default")
      (node (ref "R21") (pin "2") (pinfunction "2_2") (pintype "input"))
      (node (ref "U1") (pin "48") (pinfunction "PE1_48") (pintype "unspecified"))
      (node (ref "U4") (pin "7") (pinfunction "SDA_7") (pintype "unspecified"))
    )
    (net (code "15") (name "/LCD_BL") (class "Default")
      (node (ref "R24") (pin "1") (pinfunction "1_1") (pintype "input"))
      (node (ref "U1") (pin "43") (pinfunction "PE6_43") (pintype "unspecified"))
    )
    (net (code "16") (name "/LCD_CLK") (class "Default")
      (node (ref "FPC1") (pin "30") (pinfunction "30_30") (pintype "unspecified"))
      (node (ref "U1") (pin "26") (pinfunction "PD18_26") (pintype "unspecified"))
    )
    (net (code "17") (name "/LCD_D2") (class "Default")
      (node (ref "FPC1") (pin "23") (pinfunction "23_23") (pintype "unspecified"))
      (node (ref "U1") (pin "6") (pinfunction "PD0_6") (pintype "unspecified"))
    )
    (net (code "18") (name "/LCD_D3") (class "Default")
      (node (ref "FPC1") (pin "24") (pinfunction "24_24") (pintype "unspecified"))
      (node (ref "U1") (pin "7") (pinfunction "PD1_7") (pintype "unspecified"))
    )
    (net (code "19") (name "/LCD_D4") (class "Default")
      (node (ref "FPC1") (pin "25") (pinfunction "25_25") (pintype "unspecified"))
      (node (ref "U1") (pin "8") (pinfunction "PD2_8") (pintype "unspecified"))
    )
    (net (code "20") (name "/LCD_D5") (class "Default")
      (node (ref "FPC1") (pin "26") (pinfunction "26_26") (pintype "unspecified"))
      (node (ref "U1") (pin "9") (pinfunction "PD3_9") (pintype "unspecified"))
    )
    (net (code "21") (name "/LCD_D6") (class "Default")
      (node (ref "FPC1") (pin "27") (pinfunction "27_27") (pintype "unspecified"))
      (node (ref "U1") (pin "10") (pinfunction "PD4_10") (pintype "unspecified"))
    )
    (net (code "22") (name "/LCD_D7") (class "Default")
      (node (ref "FPC1") (pin "28") (pinfunction "28_28") (pintype "unspecified"))
      (node (ref "U1") (pin "11") (pinfunction "PD5_11") (pintype "unspecified"))
    )
    (net (code "23") (name "/LCD_D10") (class "Default")
      (node (ref "FPC1") (pin "15") (pinfunction "15_15") (pintype "unspecified"))
      (node (ref "U1") (pin "12") (pinfunction "PD6_12") (pintype "unspecified"))
    )
    (net (code "24") (name "/LCD_D11") (class "Default")
      (node (ref "FPC1") (pin "16") (pinfunction "16_16") (pintype "unspecified"))
      (node (ref "U1") (pin "13") (pinfunction "PD7_13") (pintype "unspecified"))
    )
    (net (code "25") (name "/LCD_D12") (class "Default")
      (node (ref "FPC1") (pin "17") (pinfunction "17_17") (pintype "unspecified"))
      (node (ref "U1") (pin "14") (pinfunction "PD8_14") (pintype "unspecified"))
    )
    (net (code "26") (name "/LCD_D13") (class "Default")
      (node (ref "FPC1") (pin "18") (pinfunction "18_18") (pintype "unspecified"))
      (node (ref "U1") (pin "15") (pinfunction "PD9_15") (pintype "unspecified"))
    )
    (net (code "27") (name "/LCD_D14") (class "Default")
      (node (ref "FPC1") (pin "19") (pinfunction "19_19") (pintype "unspecified"))
      (node (ref "U1") (pin "16") (pinfunction "PD10_16") (pintype "unspecified"))
    )
    (net (code "28") (name "/LCD_D15") (class "Default")
      (node (ref "FPC1") (pin "20") (pinfunction "20_20") (pintype "unspecified"))
      (node (ref "U1") (pin "17") (pinfunction "PD11_17") (pintype "unspecified"))
    )
    (net (code "29") (name "/LCD_D18") (class "Default")
      (node (ref "FPC1") (pin "7") (pinfunction "7_7") (pintype "unspecified"))
      (node (ref "U1") (pin "18") (pinfunction "PD12_18") (pintype "unspecified"))
    )
    (net (code "30") (name "/LCD_D19") (class "Default")
      (node (ref "FPC1") (pin "8") (pinfunction "8_8") (pintype "unspecified"))
      (node (ref "U1") (pin "19") (pinfunction "PD13_19") (pintype "unspecified"))
    )
    (net (code "31") (name "/LCD_D20") (class "Default")
      (node (ref "FPC1") (pin "9") (pinfunction "9_9") (pintype "unspecified"))
      (node (ref "U1") (pin "21") (pinfunction "PD14_21") (pintype "unspecified"))
    )
    (net (code "32") (name "/LCD_D21") (class "Default")
      (node (ref "FPC1") (pin "10") (pinfunction "10_10") (pintype "unspecified"))
      (node (ref "U1") (pin "23") (pinfunction "PD15_23") (pintype "unspecified"))
    )
    (net (code "33") (name "/LCD_D22") (class "Default")
      (node (ref "FPC1") (pin "11") (pinfunction "11_11") (pintype "unspecified"))
      (node (ref "U1") (pin "24") (pinfunction "PD16_24") (pintype "unspecified"))
    )
    (net (code "34") (name "/LCD_D23") (class "Default")
      (node (ref "FPC1") (pin "12") (pinfunction "12_12") (pintype "unspecified"))
      (node (ref "U1") (pin "25") (pinfunction "PD17_25") (pintype "unspecified"))
    )
    (net (code "35") (name "/LCD_DE") (class "Default")
      (node (ref "FPC1") (pin "34") (pinfunction "34_34") (pintype "unspecified"))
      (node (ref "U1") (pin "27") (pinfunction "PD19_27") (pintype "unspecified"))
    )
    (net (code "36") (name "/LCD_HSYNC") (class "Default")
      (node (ref "FPC1") (pin "32") (pinfunction "32_32") (pintype "unspecified"))
      (node (ref "U1") (pin "28") (pinfunction "PD20_28") (pintype "unspecified"))
    )
    (net (code "37") (name "/LCD_VSYNC") (class "Default")
      (node (ref "FPC1") (pin "33") (pinfunction "33_33") (pintype "unspecified"))
      (node (ref "U1") (pin "29") (pinfunction "PD21_29") (pintype "unspecified"))
    )
    (net (code "38") (name "/LED_GND") (class "Default")
      (node (ref "FPC1") (pin "1") (pinfunction "1_1") (pintype "unspecified"))
      (node (ref "R23") (pin "2") (pinfunction "2_2") (pintype "input"))
      (node (ref "U5") (pin "3") (pinfunction "FB_3") (pintype "input"))
    )
    (net (code "39") (name "/LED_VCC") (class "Default")
      (node (ref "C17") (pin "2") (pinfunction "2_2") (pintype "unspecified"))
      (node (ref "D1") (pin "1") (pinfunction "K_1") (pintype "unspecified"))
      (node (ref "FPC1") (pin "2") (pinfunction "2_2") (pintype "unspecified"))
      (node (ref "U5") (pin "5") (pinfunction "OV_5") (pintype "input"))
    )
    (net (code "40") (name "/NRST") (class "Default")
      (node (ref "C10") (pin "2") (pinfunction "2_2") (pintype "unspecified"))
      (node (ref "R3") (pin "1") (pinfunction "1_1") (pintype "input"))
      (node (ref "SW1") (pin "1") (pinfunction "A_1") (pintype "unspecified"))
      (node (ref "SW1") (pin "2") (pinfunction "B_2") (pintype "unspecified"))
      (node (ref "U1") (pin "70") (pinfunction "RESET_70") (pintype "unspecified"))
    )
    (net (code "41") (name "/SDIO_CD") (class "Default")
      (node (ref "R18") (pin "1") (pinfunction "1_1") (pintype "input"))
      (node (ref "TF1") (pin "9") (pinfunction "CD_9") (pintype "unspecified"))
      (node (ref "U1") (pin "47") (pinfunction "PE2_47") (pintype "unspecified"))
    )
    (net (code "42") (name "/SDIO_CK") (class "Default")
      (node (ref "R15") (pin "1") (pinfunction "1_1") (pintype "input"))
      (node (ref "U1") (pin "56") (pinfunction "PF2_56") (pintype "unspecified"))
    )
    (net (code "43") (name "/SDIO_CMD") (class "Default")
      (node (ref "R14") (pin "1") (pinfunction "1_1") (pintype "input"))
      (node (ref "TF1") (pin "3") (pinfunction "CMD_3") (pintype "unspecified"))
      (node (ref "U1") (pin "55") (pinfunction "PF3_55") (pintype "unspecified"))
    )
    (net (code "44") (name "/SDIO_D0") (class "Default")
      (node (ref "R16") (pin "1") (pinfunction "1_1") (pintype "input"))
      (node (ref "TF1") (pin "7") (pinfunction "DAT0_7") (pintype "unspecified"))
      (node (ref "U1") (pin "57") (pinfunction "PF1_57") (pintype "unspecified"))
    )
    (net (code "45") (name "/SDIO_D1") (class "Default")
      (node (ref "R17") (pin "1") (pinfunction "1_1") (pintype "input"))
      (node (ref "TF1") (pin "8") (pinfunction "DAT1_8") (pintype "unspecified"))
      (node (ref "U1") (pin "58") (pinfunction "PF0_58") (pintype "unspecified"))
    )
    (net (code "46") (name "/SDIO_D2") (class "Default")
      (node (ref "R12") (pin "1") (pinfunction "1_1") (pintype "input"))
      (node (ref "TF1") (pin "1") (pinfunction "DAT2_1") (pintype "unspecified"))
      (node (ref "U1") (pin "53") (pinfunction "PF5_53") (pintype "unspecified"))
    )
    (net (code "47") (name "/SDIO_D3") (class "Default")
      (node (ref "R13") (pin "1") (pinfunction "1_1") (pintype "input"))
      (node (ref "TF1") (pin "2") (pinfunction "CD/DAT3_2") (pintype "unspecified"))
      (node (ref "U1") (pin "54") (pinfunction "PF4_54") (pintype "unspecified"))
    )
    (net (code "48") (name "/SPI0_CS") (class "Default")
      (node (ref "SW2") (pin "1") (pinfunction "A_1") (pintype "unspecified"))
      (node (ref "SW2") (pin "2") (pinfunction "B_2") (pintype "unspecified"))
      (node (ref "U1") (pin "60") (pinfunction "PC1_60") (pintype "unspecified"))
      (node (ref "U3") (pin "1") (pinfunction "CS#_1") (pintype "unspecified"))
    )
    (net (code "49") (name "/SPI0_MISO") (class "Default")
      (node (ref "U1") (pin "61") (pinfunction "PC2_61") (pintype "unspecified"))
      (node (ref "U3") (pin "2") (pinfunction "DO_2") (pintype "unspecified"))
    )
    (net (code "50") (name "/SPI0_MOSI") (class "Default")
      (node (ref "U1") (pin "62") (pinfunction "PC3_62") (pintype "unspecified"))
      (node (ref "U3") (pin "5") (pinfunction "DI_5") (pintype "unspecified"))
    )
    (net (code "51") (name "/SPI0_SCK") (class "Default")
      (node (ref "U1") (pin "59") (pinfunction "PC0_59") (pintype "unspecified"))
      (node (ref "U3") (pin "6") (pinfunction "CLK_6") (pintype "unspecified"))
    )
    (net (code "52") (name "/SVREF") (class "Default")
      (node (ref "C8") (pin "2") (pinfunction "2_2") (pintype "unspecified"))
      (node (ref "C9") (pin "2") (pinfunction "2_2") (pintype "unspecified"))
      (node (ref "R1") (pin "2") (pinfunction "2_2") (pintype "input"))
      (node (ref "R2") (pin "2") (pinfunction "2_2") (pintype "input"))
      (node (ref "U1") (pin "33") (pinfunction "SVREF_33") (pintype "unspecified"))
    )
    (net (code "53") (name "/UART1_RX") (class "Default")
      (node (ref "LED2") (pin "1") (pinfunction "C_1") (pintype "input"))
      (node (ref "U1") (pin "64") (pinfunction "TPY1_64") (pintype "unspecified"))
      (node (ref "U2") (pin "6") (pinfunction "TXD_6") (pintype "unspecified"))
    )
    (net (code "54") (name "/UART1_TX") (class "Default")
      (node (ref "LED3") (pin "1") (pinfunction "C_1") (pintype "input"))
      (node (ref "U1") (pin "63") (pinfunction "TPY2_63") (pintype "unspecified"))
      (node (ref "U2") (pin "7") (pinfunction "RXD_7") (pintype "unspecified"))
    )
    (net (code "55") (name "/USB_DN") (class "Default")
      (node (ref "U1") (pin "68") (pinfunction "USB-DM_68") (pintype "unspecified"))
      (node (ref "USB2") (pin "5") (pinfunction "DN2_5") (pintype "unspecified"))
      (node (ref "USB2") (pin "7") (pinfunction "DN1_7") (pintype "unspecified"))
    )
    (net (code "56") (name "/USB_DP") (class "Default")
      (node (ref "U1") (pin "69") (pinfunction "USB-DP_69") (pintype "unspecified"))
      (node (ref "USB2") (pin "6") (pinfunction "DP1_6") (pintype "unspecified"))
      (node (ref "USB2") (pin "8") (pinfunction "DP2_8") (pintype "unspecified"))
    )
    (net (code "57") (name "/WORK_LED") (class "Default")
      (node (ref "LED1") (pin "1") (pinfunction "K_1") (pintype "input"))
      (node (ref "U1") (pin "44") (pinfunction "PE5_44") (pintype "unspecified"))
    )
    (net (code "58") (name "/XI") (class "Default")
      (node (ref "C12") (pin "2") (pinfunction "2_2") (pintype "input"))
      (node (ref "R4") (pin "2") (pinfunction "2_2") (pintype "input"))
      (node (ref "U1") (pin "51") (pinfunction "HOSCI_51") (pintype "unspecified"))
      (node (ref "X1") (pin "3") (pinfunction "OSC2_3") (pintype "unspecified"))
    )
    (net (code "59") (name "/XO") (class "Default")
      (node (ref "C11") (pin "1") (pinfunction "1_1") (pintype "input"))
      (node (ref "R4") (pin "1") (pinfunction "1_1") (pintype "input"))
      (node (ref "U1") (pin "52") (pinfunction "HOSCO_52") (pintype "unspecified"))
      (node (ref "X1") (pin "1") (pinfunction "OSC1_1") (pintype "unspecified"))
    )
    (net (code "60") (name "GND") (class "Default")
      (node (ref "B1") (pin "2") (pinfunction "2_2") (pintype "input"))
      (node (ref "C1") (pin "1") (pinfunction "1_1") (pintype "unspecified"))
      (node (ref "C10") (pin "1") (pinfunction "1_1") (pintype "unspecified"))
      (node (ref "C11") (pin "2") (pinfunction "2_2") (pintype "input"))
      (node (ref "C12") (pin "1") (pinfunction "1_1") (pintype "input"))
      (node (ref "C13") (pin "2") (pinfunction "2_2") (pintype "unspecified"))
      (node (ref "C14") (pin "1") (pinfunction "1_1") (pintype "unspecified"))
      (node (ref "C15") (pin "2") (pinfunction "2_2") (pintype "unspecified"))
      (node (ref "C16") (pin "1") (pinfunction "1_1") (pintype "unspecified"))
      (node (ref "C17") (pin "1") (pinfunction "1_1") (pintype "unspecified"))
      (node (ref "C18") (pin "1") (pinfunction "1_1") (pintype "unspecified"))
      (node (ref "C19") (pin "2") (pinfunction "2_2") (pintype "unspecified"))
      (node (ref "C2") (pin "1") (pinfunction "1_1") (pintype "unspecified"))
      (node (ref "C20") (pin "2") (pinfunction "2_2") (pintype "unspecified"))
      (node (ref "C21") (pin "1") (pinfunction "1_1") (pintype "unspecified"))
      (node (ref "C22") (pin "2") (pinfunction "2_2") (pintype "unspecified"))
      (node (ref "C23") (pin "1") (pinfunction "1_1") (pintype "unspecified"))
      (node (ref "C24") (pin "2") (pinfunction "2_2") (pintype "unspecified"))
      (node (ref "C25") (pin "1") (pinfunction "1_1") (pintype "unspecified"))
      (node (ref "C26") (pin "2") (pinfunction "2_2") (pintype "unspecified"))
      (node (ref "C27") (pin "1") (pinfunction "1_1") (pintype "unspecified"))
      (node (ref "C3") (pin "1") (pinfunction "1_1") (pintype "unspecified"))
      (node (ref "C4") (pin "1") (pinfunction "1_1") (pintype "unspecified"))
      (node (ref "C5") (pin "1") (pinfunction "1_1") (pintype "unspecified"))
      (node (ref "C6") (pin "1") (pinfunction "1_1") (pintype "unspecified"))
      (node (ref "C7") (pin "1") (pinfunction "1_1") (pintype "unspecified"))
      (node (ref "C9") (pin "1") (pinfunction "1_1") (pintype "unspecified"))
      (node (ref "FPC1") (pin "13") (pinfunction "13_13") (pintype "unspecified"))
      (node (ref "FPC1") (pin "14") (pinfunction "14_14") (pintype "unspecified"))
      (node (ref "FPC1") (pin "21") (pinfunction "21_21") (pintype "unspecified"))
      (node (ref "FPC1") (pin "22") (pinfunction "22_22") (pintype "unspecified"))
      (node (ref "FPC1") (pin "29") (pinfunction "29_29") (pintype "unspecified"))
      (node (ref "FPC1") (pin "3") (pinfunction "3_3") (pintype "unspecified"))
      (node (ref "FPC1") (pin "36") (pinfunction "36_36") (pintype "unspecified"))
      (node (ref "FPC1") (pin "5") (pinfunction "5_5") (pintype "unspecified"))
      (node (ref "FPC1") (pin "6") (pinfunction "6_6") (pintype "unspecified"))
      (node (ref "FPC2") (pin "4") (pinfunction "4_4") (pintype "unspecified"))
      (node (ref "Q1") (pin "2") (pinfunction "E_2") (pintype "unspecified"))
      (node (ref "R10") (pin "1") (pinfunction "1_1") (pintype "input"))
      (node (ref "R11") (pin "1") (pinfunction "1_1") (pintype "input"))
      (node (ref "R2") (pin "1") (pinfunction "1_1") (pintype "input"))
      (node (ref "R23") (pin "1") (pinfunction "1_1") (pintype "input"))
      (node (ref "R25") (pin "2") (pinfunction "2_2") (pintype "input"))
      (node (ref "R27") (pin "2") (pinfunction "2_2") (pintype "input"))
      (node (ref "R8") (pin "1") (pinfunction "1_1") (pintype "input"))
      (node (ref "R9") (pin "1") (pinfunction "1_1") (pintype "input"))
      (node (ref "SW1") (pin "3") (pinfunction "C_3") (pintype "unspecified"))
      (node (ref "SW1") (pin "4") (pinfunction "D_4") (pintype "unspecified"))
      (node (ref "SW2") (pin "3") (pinfunction "C_3") (pintype "unspecified"))
      (node (ref "SW2") (pin "4") (pinfunction "D_4") (pintype "unspecified"))
      (node (ref "TF1") (pin "10") (pinfunction "GND_10") (pintype "unspecified"))
      (node (ref "TF1") (pin "11") (pinfunction "GND_11") (pintype "unspecified"))
      (node (ref "TF1") (pin "12") (pinfunction "GND_12") (pintype "unspecified"))
      (node (ref "TF1") (pin "13") (pinfunction "GND_13") (pintype "unspecified"))
      (node (ref "TF1") (pin "6") (pinfunction "VSS_6") (pintype "unspecified"))
      (node (ref "U1") (pin "74") (pinfunction "TVGND_74") (pintype "unspecified"))
      (node (ref "U1") (pin "82") (pinfunction "AGND_82") (pintype "unspecified"))
      (node (ref "U1") (pin "89") (pinfunction "GND_89") (pintype "unspecified"))
      (node (ref "U2") (pin "3") (pinfunction "GND_3") (pintype "unspecified"))
      (node (ref "U3") (pin "3") (pinfunction "IO2_3") (pintype "unspecified"))
      (node (ref "U3") (pin "4") (pinfunction "GND_4") (pintype "unspecified"))
      (node (ref "U4") (pin "5") (pinfunction "GND_5") (pintype "unspecified"))
      (node (ref "U5") (pin "2") (pinfunction "GND_2") (pintype "input"))
      (node (ref "U6") (pin "1") (pinfunction "GND_1") (pintype "unspecified"))
      (node (ref "U7") (pin "1") (pinfunction "VSS_1") (pintype "unspecified"))
      (node (ref "U8") (pin "1") (pinfunction "VSS_1") (pintype "unspecified"))
      (node (ref "U9") (pin "1") (pinfunction "GND_1") (pintype "input"))
      (node (ref "USB1") (pin "1") (pinfunction "GND_1") (pintype "unspecified"))
      (node (ref "USB1") (pin "12") (pinfunction "GND_12") (pintype "unspecified"))
      (node (ref "USB2") (pin "1") (pinfunction "GND_1") (pintype "unspecified"))
      (node (ref "USB2") (pin "12") (pinfunction "GND_12") (pintype "unspecified"))
      (node (ref "X1") (pin "2") (pinfunction "2_2") (pintype "unspecified"))
      (node (ref "X1") (pin "4") (pinfunction "4_4") (pintype "unspecified"))
    )
    (net (code "61") (name "Net-(D1-A)") (class "Default")
      (node (ref "D1") (pin "2") (pinfunction "A_2") (pintype "unspecified"))
      (node (ref "L1") (pin "1") (pinfunction "1_1") (pintype "input"))
      (node (ref "U5") (pin "1") (pinfunction "SW_1") (pintype "input"))
    )
    (net (code "62") (name "Net-(LED1-A)") (class "Default")
      (node (ref "LED1") (pin "2") (pinfunction "A_2") (pintype "input"))
      (node (ref "R5") (pin "2") (pinfunction "2_2") (pintype "input"))
    )
    (net (code "63") (name "Net-(LED2-A)") (class "Default")
      (node (ref "LED2") (pin "2") (pinfunction "A_2") (pintype "input"))
      (node (ref "R6") (pin "2") (pinfunction "2_2") (pintype "input"))
    )
    (net (code "64") (name "Net-(LED3-A)") (class "Default")
      (node (ref "LED3") (pin "2") (pinfunction "A_2") (pintype "input"))
      (node (ref "R7") (pin "2") (pinfunction "2_2") (pintype "input"))
    )
    (net (code "65") (name "Net-(Q1-B)") (class "Default")
      (node (ref "Q1") (pin "1") (pinfunction "B_1") (pintype "unspecified"))
      (node (ref "R26") (pin "1") (pinfunction "1_1") (pintype "input"))
      (node (ref "R27") (pin "1") (pinfunction "1_1") (pintype "input"))
    )
    (net (code "66") (name "Net-(Q1-C)") (class "Default")
      (node (ref "BUZZER1") (pin "2") (pinfunction "2_2") (pintype "unspecified"))
      (node (ref "Q1") (pin "3") (pinfunction "C_3") (pintype "unspecified"))
    )
    (net (code "67") (name "Net-(TF1-CLK)") (class "Default")
      (node (ref "R15") (pin "2") (pinfunction "2_2") (pintype "input"))
      (node (ref "TF1") (pin "5") (pinfunction "CLK_5") (pintype "unspecified"))
    )
    (net (code "68") (name "Net-(U4-VBAT)") (class "Default")
      (node (ref "B1") (pin "1") (pinfunction "1_1") (pintype "input"))
      (node (ref "U4") (pin "6") (pinfunction "VBAT_6") (pintype "unspecified"))
    )
    (net (code "69") (name "Net-(U5-EN)") (class "Default")
      (node (ref "R24") (pin "2") (pinfunction "2_2") (pintype "input"))
      (node (ref "R25") (pin "1") (pinfunction "1_1") (pintype "input"))
      (node (ref "U5") (pin "4") (pinfunction "EN_4") (pintype "input"))
    )
    (net (code "70") (name "Net-(USB1-CC1)") (class "Default")
      (node (ref "R8") (pin "2") (pinfunction "2_2") (pintype "input"))
      (node (ref "USB1") (pin "4") (pinfunction "CC1_4") (pintype "unspecified"))
    )
    (net (code "71") (name "Net-(USB1-CC2)") (class "Default")
      (node (ref "R9") (pin "2") (pinfunction "2_2") (pintype "input"))
      (node (ref "USB1") (pin "10") (pinfunction "CC2_10") (pintype "unspecified"))
    )
    (net (code "72") (name "Net-(USB2-CC1)") (class "Default")
      (node (ref "R10") (pin "2") (pinfunction "2_2") (pintype "input"))
      (node (ref "USB2") (pin "4") (pinfunction "CC1_4") (pintype "unspecified"))
    )
    (net (code "73") (name "Net-(USB2-CC2)") (class "Default")
      (node (ref "R11") (pin "2") (pinfunction "2_2") (pintype "input"))
      (node (ref "USB2") (pin "10") (pinfunction "CC2_10") (pintype "unspecified"))
    )
    (net (code "74") (name "unconnected-(FPC1-Pad35)") (class "Default")
      (node (ref "FPC1") (pin "35") (pinfunction "35_35") (pintype "unspecified+no_connect"))
    )
    (net (code "75") (name "unconnected-(FPC1-Pad37)") (class "Default")
      (node (ref "FPC1") (pin "37") (pinfunction "37_37") (pintype "unspecified+no_connect"))
    )
    (net (code "76") (name "unconnected-(FPC1-Pad38)") (class "Default")
      (node (ref "FPC1") (pin "38") (pinfunction "38_38") (pintype "unspecified+no_connect"))
    )
    (net (code "77") (name "unconnected-(FPC1-Pad39)") (class "Default")
      (node (ref "FPC1") (pin "39") (pinfunction "39_39") (pintype "unspecified+no_connect"))
    )
    (net (code "78") (name "unconnected-(FPC1-Pad40)") (class "Default")
      (node (ref "FPC1") (pin "40") (pinfunction "40_40") (pintype "unspecified+no_connect"))
    )
    (net (code "79") (name "unconnected-(FPC1-Pad41)") (class "Default")
      (node (ref "FPC1") (pin "41") (pinfunction "41_41") (pintype "unspecified+no_connect"))
    )
    (net (code "80") (name "unconnected-(FPC1-Pad42)") (class "Default")
      (node (ref "FPC1") (pin "42") (pinfunction "42_42") (pintype "unspecified+no_connect"))
    )
    (net (code "81") (name "unconnected-(FPC2-Pad7)") (class "Default")
      (node (ref "FPC2") (pin "7") (pinfunction "7_7") (pintype "unspecified+no_connect"))
    )
    (net (code "82") (name "unconnected-(FPC2-Pad8)") (class "Default")
      (node (ref "FPC2") (pin "8") (pinfunction "8_8") (pintype "unspecified+no_connect"))
    )
    (net (code "83") (name "unconnected-(U1-FMINL-Pad84)") (class "Default")
      (node (ref "U1") (pin "84") (pinfunction "FMINL_84") (pintype "unspecified+no_connect"))
    )
    (net (code "84") (name "unconnected-(U1-FMINR-Pad85)") (class "Default")
      (node (ref "U1") (pin "85") (pinfunction "FMINR_85") (pintype "unspecified+no_connect"))
    )
    (net (code "85") (name "unconnected-(U1-HIPCOMFB-Pad2)") (class "Default")
      (node (ref "U1") (pin "2") (pinfunction "HIPCOMFB_2") (pintype "unspecified+no_connect"))
    )
    (net (code "86") (name "unconnected-(U1-HPCOM-Pad3)") (class "Default")
      (node (ref "U1") (pin "3") (pinfunction "HPCOM_3") (pintype "unspecified+no_connect"))
    )
    (net (code "87") (name "unconnected-(U1-HPL-Pad1)") (class "Default")
      (node (ref "U1") (pin "1") (pinfunction "HPL_1") (pintype "unspecified+no_connect"))
    )
    (net (code "88") (name "unconnected-(U1-HPR-Pad88)") (class "Default")
      (node (ref "U1") (pin "88") (pinfunction "HPR_88") (pintype "unspecified+no_connect"))
    )
    (net (code "89") (name "unconnected-(U1-LINL-Pad86)") (class "Default")
      (node (ref "U1") (pin "86") (pinfunction "LINL_86") (pintype "unspecified+no_connect"))
    )
    (net (code "90") (name "unconnected-(U1-LRADC0-Pad79)") (class "Default")
      (node (ref "U1") (pin "79") (pinfunction "LRADC0_79") (pintype "unspecified+no_connect"))
    )
    (net (code "91") (name "unconnected-(U1-MICIN-Pad87)") (class "Default")
      (node (ref "U1") (pin "87") (pinfunction "MICIN_87") (pintype "unspecified+no_connect"))
    )
    (net (code "92") (name "unconnected-(U1-PE3-Pad46)") (class "Default")
      (node (ref "U1") (pin "46") (pinfunction "PE3_46") (pintype "unspecified+no_connect"))
    )
    (net (code "93") (name "unconnected-(U1-PE7-Pad42)") (class "Default")
      (node (ref "U1") (pin "42") (pinfunction "PE7_42") (pintype "unspecified+no_connect"))
    )
    (net (code "94") (name "unconnected-(U1-PE8-Pad41)") (class "Default")
      (node (ref "U1") (pin "41") (pinfunction "PE8_41") (pintype "unspecified+no_connect"))
    )
    (net (code "95") (name "unconnected-(U1-TPX1-Pad66)") (class "Default")
      (node (ref "U1") (pin "66") (pinfunction "TPX1_66") (pintype "unspecified+no_connect"))
    )
    (net (code "96") (name "unconnected-(U1-TPX2-Pad65)") (class "Default")
      (node (ref "U1") (pin "65") (pinfunction "TPX2_65") (pintype "unspecified+no_connect"))
    )
    (net (code "97") (name "unconnected-(U1-TVIN0-Pad78)") (class "Default")
      (node (ref "U1") (pin "78") (pinfunction "TVIN0_78") (pintype "unspecified+no_connect"))
    )
    (net (code "98") (name "unconnected-(U1-TVIN1-Pad77)") (class "Default")
      (node (ref "U1") (pin "77") (pinfunction "TVIN1_77") (pintype "unspecified+no_connect"))
    )
    (net (code "99") (name "unconnected-(U1-TVOUT-Pad72)") (class "Default")
      (node (ref "U1") (pin "72") (pinfunction "TVOUT_72") (pintype "unspecified+no_connect"))
    )
    (net (code "100") (name "unconnected-(U1-TV_VRN-Pad75)") (class "Default")
      (node (ref "U1") (pin "75") (pinfunction "TV_VRN_75") (pintype "unspecified+no_connect"))
    )
    (net (code "101") (name "unconnected-(U1-TV_VRP-Pad76)") (class "Default")
      (node (ref "U1") (pin "76") (pinfunction "TV_VRP_76") (pintype "unspecified+no_connect"))
    )
    (net (code "102") (name "unconnected-(U1-VRA1-Pad81)") (class "Default")
      (node (ref "U1") (pin "81") (pinfunction "VRA1_81") (pintype "unspecified+no_connect"))
    )
    (net (code "103") (name "unconnected-(U1-VRA2-Pad83)") (class "Default")
      (node (ref "U1") (pin "83") (pinfunction "VRA2_83") (pintype "unspecified+no_connect"))
    )
    (net (code "104") (name "unconnected-(U2-RTS#-Pad4)") (class "Default")
      (node (ref "U2") (pin "4") (pinfunction "RTS#_4") (pintype "unspecified+no_connect"))
    )
    (net (code "105") (name "unconnected-(U4-F32K-Pad1)") (class "Default")
      (node (ref "U4") (pin "1") (pinfunction "F32K_1") (pintype "unspecified+no_connect"))
    )
    (net (code "106") (name "unconnected-(U4-INT-Pad3)") (class "Default")
      (node (ref "U4") (pin "3") (pinfunction "INT_3") (pintype "unspecified+no_connect"))
    )
    (net (code "107") (name "unconnected-(U4-NC-Pad4)") (class "Default")
      (node (ref "U4") (pin "4") (pinfunction "NC_4") (pintype "unspecified+no_connect"))
    )
    (net (code "108") (name "unconnected-(USB1-SBU1-Pad9)") (class "Default")
      (node (ref "USB1") (pin "9") (pinfunction "SBU1_9") (pintype "unspecified+no_connect"))
    )
    (net (code "109") (name "unconnected-(USB1-SBU2-Pad3)") (class "Default")
      (node (ref "USB1") (pin "3") (pinfunction "SBU2_3") (pintype "unspecified+no_connect"))
    )
    (net (code "110") (name "unconnected-(USB1-SHELL-Pad13)") (class "Default")
      (node (ref "USB1") (pin "13") (pinfunction "SHELL_13") (pintype "unspecified+no_connect"))
    )
    (net (code "111") (name "unconnected-(USB1-SHELL-Pad14)") (class "Default")
      (node (ref "USB1") (pin "14") (pinfunction "SHELL_14") (pintype "unspecified+no_connect"))
    )
    (net (code "112") (name "unconnected-(USB2-SBU1-Pad9)") (class "Default")
      (node (ref "USB2") (pin "9") (pinfunction "SBU1_9") (pintype "unspecified+no_connect"))
    )
    (net (code "113") (name "unconnected-(USB2-SBU2-Pad3)") (class "Default")
      (node (ref "USB2") (pin "3") (pinfunction "SBU2_3") (pintype "unspecified+no_connect"))
    )
    (net (code "114") (name "unconnected-(USB2-SHELL-Pad13)") (class "Default")
      (node (ref "USB2") (pin "13") (pinfunction "SHELL_13") (pintype "unspecified+no_connect"))
    )
    (net (code "115") (name "unconnected-(USB2-SHELL-Pad14)") (class "Default")
      (node (ref "USB2") (pin "14") (pinfunction "SHELL_14") (pintype "unspecified+no_connect"))
    )
  )
)
